# Power_Battery_Charger.net
KiCad netlist of a schematic drawn in Altium Designer
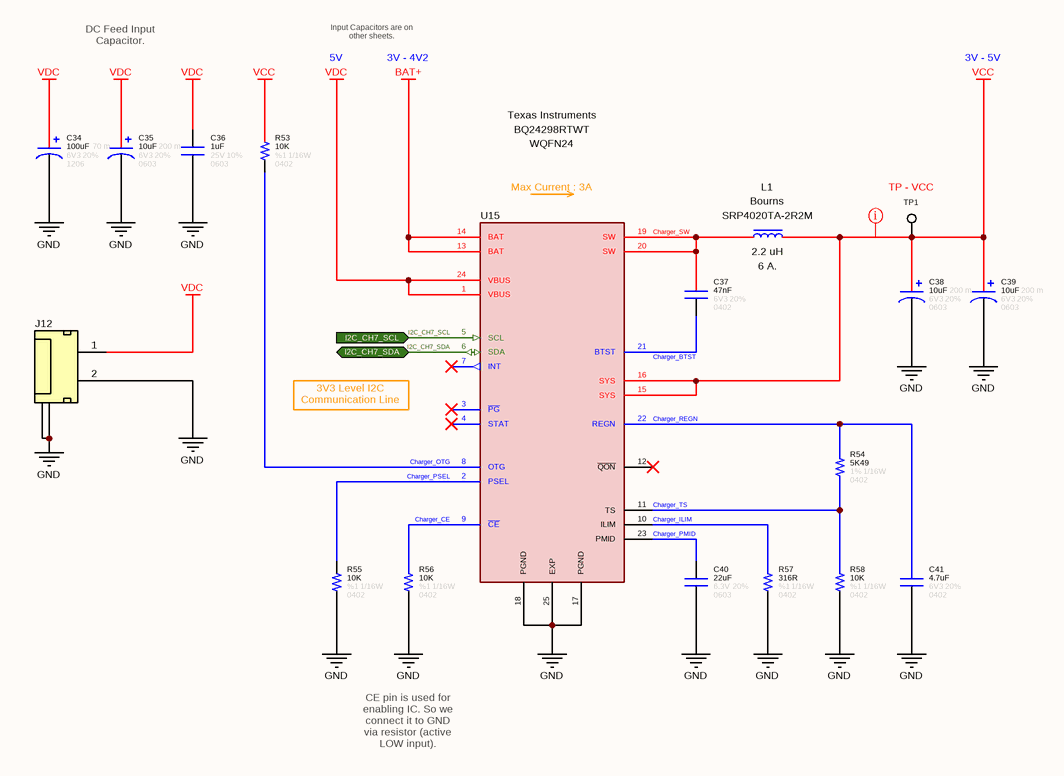
[diagram p0: Power Battery Charger.SchDoc]

(export (version "E")
  (design (tool "Eeschema 10.0.6"))
  (components
    (comp (ref "C34")
      (value "100uF")
      (footprint "CAPACITOR_0603_Tantalum")
      (description "Tantalum Capacitors - Polymer 6.3V 100uF 1206 20% ESR=70mOhms")
      (fields
        (field (name "MANUFACTURER PART NUMBER") "T527I107M006ATE070")
        (field (name "ESR") "70 m")
        (field (name "TOLERANCE") "20%")
        (field (name "CASE") "1206")
        (field (name "VOLTAGE") "6V3")
        (field (name "Comment") "Capacitor - 100uF [1206] (Tantalum)")
      )
      (libsource (lib "Akkoyun") (part "Capacitor - 100uF [1206-6V3] (Tantalium)"))
    )
    (comp (ref "C35")
      (value "10uF")
      (footprint "CAPACITOR_0603_Tantalum")
      (description "Capacitor - 10uF [0603] (Tantalium)")
      (fields
        (field (name "MANUFACTURER PART NUMBER") "F380J106MMAAH3")
        (field (name "ESR") "200 m")
        (field (name "TOLERANCE") "20%")
        (field (name "CASE") "0603")
        (field (name "VOLTAGE") "6V3")
        (field (name "Comment") "Capacitor - 10uF [0603] (Tantalum)")
      )
      (libsource (lib "Akkoyun") (part "Capacitor - 10uF [0603-6V3] (Tantalium)"))
    )
    (comp (ref "C36")
      (value "1uF")
      (footprint "CAPACITOR_0603")
      (description "Multilayer Ceramic Capacitors - SMD - 25V 1uF X7R 0603 10%")
      (fields
        (field (name "MANUFACTURER PART NUMBER") "GCJ188R71E105KA01D")
        (field (name "TOLERANCE") "10%")
        (field (name "CASE") "0603")
        (field (name "VOLTAGE") "25V")
        (field (name "Comment") "Capacitor - 1uF [0603] (Ceramic)")
      )
      (libsource (lib "Akkoyun") (part "Capacitor - 1uF [0603-25V]"))
    )
    (comp (ref "C37")
      (value "47nF")
      (footprint "CAPACITOR_0402")
      (description "Multilayer Ceramic Capacitors - SMD - 6.3V 47nF X7R 0402 10%")
      (fields
        (field (name "MANUFACTURER PART NUMBER") "04026C472MAT2A")
        (field (name "TOLERANCE") "20%")
        (field (name "CASE") "0402")
        (field (name "VOLTAGE") "6V3")
        (field (name "Comment") "Capacitor - 47nF [0402] (Ceramic)")
      )
      (libsource (lib "Akkoyun") (part "Capacitor - 47nF [0402-6V3]"))
    )
    (comp (ref "C38")
      (value "10uF")
      (footprint "CAPACITOR_0603_Tantalum")
      (description "Capacitor - 10uF [0603] (Tantalium)")
      (fields
        (field (name "MANUFACTURER PART NUMBER") "F380J106MMAAH3")
        (field (name "ESR") "200 m")
        (field (name "TOLERANCE") "20%")
        (field (name "CASE") "0603")
        (field (name "VOLTAGE") "6V3")
        (field (name "Comment") "Capacitor - 10uF [0603] (Tantalum)")
      )
      (libsource (lib "Akkoyun") (part "Capacitor - 10uF [0603-6V3] (Tantalium)"))
    )
    (comp (ref "C39")
      (value "10uF")
      (footprint "CAPACITOR_0603_Tantalum")
      (description "Capacitor - 10uF [0603] (Tantalium)")
      (fields
        (field (name "MANUFACTURER PART NUMBER") "F380J106MMAAH3")
        (field (name "ESR") "200 m")
        (field (name "TOLERANCE") "20%")
        (field (name "CASE") "0603")
        (field (name "VOLTAGE") "6V3")
        (field (name "Comment") "Capacitor - 10uF [0603] (Tantalum)")
      )
      (libsource (lib "Akkoyun") (part "Capacitor - 10uF [0603-6V3] (Tantalium)"))
    )
    (comp (ref "C40")
      (value "22uF")
      (footprint "CAPACITOR_0603")
      (description "Multilayer Ceramic Capacitors - SMD - 6V3 22uF X5R 0603 20%")
      (fields
        (field (name "MANUFACTURER PART NUMBER") "GRM188R60J226MEA0D")
        (field (name "TOLERANCE") "20%")
        (field (name "CASE") "0603")
        (field (name "VOLTAGE") "6.3V")
        (field (name "Comment") "Capacitor - 22uF [0603] (Ceramic)")
      )
      (libsource (lib "Akkoyun") (part "Capacitor - 22uF [0603-6V3]"))
    )
    (comp (ref "C41")
      (value "4.7uF")
      (footprint "CAPACITOR_0402")
      (description "Multilayer Ceramic Capacitors - SMD - 6V3 4.7uF X5R 0402 20%")
      (fields
        (field (name "MANUFACTURER PART NUMBER") "C0402C475M9PACTU")
        (field (name "TOLERANCE") "20%")
        (field (name "CASE") "0402")
        (field (name "VOLTAGE") "6V3")
        (field (name "Comment") "Capacitor - 4.7uF [0402] (Ceramic)")
      )
      (libsource (lib "Akkoyun") (part "Capacitor - 4.7uF [0402-6V3]"))
    )
    (comp (ref "J12")
      (value "2P SMD Tunic Connector")
      (footprint "Connector_Tunic 2P")
      (description "Mini Tunic Connector with 2P")
      (fields
        (field (name "MANUFACTURER PART NUMBER") "53261-0271")
        (field (name "MOUSER PART NUMBER") "538-53261-0271")
      )
      (libsource (lib "Akkoyun") (part "Connector - Mini Tunic 2P (1.25)"))
    )
    (comp (ref "L1")
      (value "2.2 uH")
      (footprint "SRP4020TA")
      (description "6 A. 2.2uH Power inducator, 20% tol, SMD, RoHS")
      (fields
        (field (name "TOLERANCE") "20%")
        (field (name "MANUFACTURER NAME") "Bourns")
        (field (name "MANUFACTURER PART NUMBER") "SRP4020TA-2R2M")
        (field (name "MAXIMUM DC CURRENT") "6 A.")
        (field (name "Comment") "SRP4020TA-2R2M")
      )
      (libsource (lib "Akkoyun") (part "Inductor - SRP4020TA-2R2M"))
    )
    (comp (ref "R53")
      (value "10K")
      (footprint "RESISTOR_0402")
      (description "Thick Film Resistors - SMD 1/16 W 10 KOhm 1%")
      (fields
        (field (name "MANUFACTURER PART NUMBER") "CRCW040210K0FKED")
        (field (name "TOLERANCE") "%1")
        (field (name "CASE") "0402")
        (field (name "POWER") "1/16W")
        (field (name "Comment") "10K - 0402 - %1 - 1/16W")
      )
      (libsource (lib "Akkoyun") (part "Resistor - 10K [0402]"))
    )
    (comp (ref "R54")
      (value "5K49")
      (footprint "RESISTOR_0402")
      (description "Thick Film Resistors - SMD 1/16 W 5.49 KOhm 1%")
      (fields
        (field (name "MANUFACTURER PART NUMBER") "CRCW04025K49FKED")
        (field (name "POWER") "1/16W")
        (field (name "CASE") "0402")
        (field (name "TOLERANCE") "1%")
        (field (name "Comment") "5K49 - 0402 - %1 - 1/16W")
      )
      (libsource (lib "Akkoyun") (part "Resistor - 5K49 [0402]"))
    )
    (comp (ref "R55")
      (value "10K")
      (footprint "RESISTOR_0402")
      (description "Thick Film Resistors - SMD 1/16 W 10 KOhm 1%")
      (fields
        (field (name "MANUFACTURER PART NUMBER") "CRCW040210K0FKED")
        (field (name "TOLERANCE") "%1")
        (field (name "CASE") "0402")
        (field (name "POWER") "1/16W")
        (field (name "Comment") "10K - 0402 - %1 - 1/16W")
      )
      (libsource (lib "Akkoyun") (part "Resistor - 10K [0402]"))
    )
    (comp (ref "R56")
      (value "10K")
      (footprint "RESISTOR_0402")
      (description "Thick Film Resistors - SMD 1/16 W 10 KOhm 1%")
      (fields
        (field (name "MANUFACTURER PART NUMBER") "CRCW040210K0FKED")
        (field (name "TOLERANCE") "%1")
        (field (name "CASE") "0402")
        (field (name "POWER") "1/16W")
        (field (name "Comment") "10K - 0402 - %1 - 1/16W")
      )
      (libsource (lib "Akkoyun") (part "Resistor - 10K [0402]"))
    )
    (comp (ref "R57")
      (value "316R")
      (footprint "RESISTOR_0402")
      (description "Thick Film Resistors - SMD 1/16 W 316 Ohm 1%")
      (fields
        (field (name "MANUFACTURER PART NUMBER") "CRCW0402316RFKED")
        (field (name "POWER") "1/16W")
        (field (name "CASE") "0402")
        (field (name "TOLERANCE") "%1")
        (field (name "Comment") "316R - 0402 - %1 - 1/16W")
      )
      (libsource (lib "Akkoyun") (part "Resistor - 316R [0402]"))
    )
    (comp (ref "R58")
      (value "10K")
      (footprint "RESISTOR_0402")
      (description "Thick Film Resistors - SMD 1/16 W 10 KOhm 1%")
      (fields
        (field (name "MANUFACTURER PART NUMBER") "CRCW040210K0FKED")
        (field (name "TOLERANCE") "%1")
        (field (name "CASE") "0402")
        (field (name "POWER") "1/16W")
        (field (name "Comment") "10K - 0402 - %1 - 1/16W")
      )
      (libsource (lib "Akkoyun") (part "Resistor - 10K [0402]"))
    )
    (comp (ref "TP1")
      (value "TP - VCC")
      (footprint "TP")
      (description "Test Point")
      (libsource (lib "Akkoyun") (part "PCB - Test Point"))
    )
    (comp (ref "U15")
      (value "BQ24298RTWT")
      (footprint "WQFN-24")
      (description "I2C Controlled 3A Single Cell Charger")
      (fields
        (field (name "MANUFACTURER NAME") "Texas Instruments")
        (field (name "MANUFACTURER PART NUMBER") "BQ24298RTWT")
        (field (name "CASE") "WQFN24")
      )
      (libsource (lib "Akkoyun") (part "IC - BQ24298RTWT"))
    )
  )
  (nets
    (net (code "1") (name "/Charger_BTST") (class "Default")
      (node (ref "C37") (pin "1") (pinfunction "1_1") (pintype "passive"))
      (node (ref "U15") (pin "21") (pinfunction "BTST_21") (pintype "power_in"))
    )
    (net (code "2") (name "/Charger_CE") (class "Default")
      (node (ref "R56") (pin "2") (pinfunction "2_2") (pintype "passive"))
      (node (ref "U15") (pin "9") (pinfunction "~{CE}_9") (pintype "passive"))
    )
    (net (code "3") (name "/Charger_ILIM") (class "Default")
      (node (ref "R57") (pin "2") (pinfunction "2_2") (pintype "passive"))
      (node (ref "U15") (pin "10") (pinfunction "ILIM_10") (pintype "passive"))
    )
    (net (code "4") (name "/Charger_OTG") (class "Default")
      (node (ref "R53") (pin "1") (pinfunction "1_1") (pintype "passive"))
      (node (ref "U15") (pin "8") (pinfunction "OTG_8") (pintype "passive"))
    )
    (net (code "5") (name "/Charger_PMID") (class "Default")
      (node (ref "C40") (pin "2") (pinfunction "2_2") (pintype "passive"))
      (node (ref "U15") (pin "23") (pinfunction "PMID_23") (pintype "power_in"))
    )
    (net (code "6") (name "/Charger_PSEL") (class "Default")
      (node (ref "R55") (pin "2") (pinfunction "2_2") (pintype "passive"))
      (node (ref "U15") (pin "2") (pinfunction "PSEL_2") (pintype "passive"))
    )
    (net (code "7") (name "/Charger_REGN") (class "Default")
      (node (ref "C41") (pin "2") (pinfunction "2_2") (pintype "passive"))
      (node (ref "R54") (pin "2") (pinfunction "2_2") (pintype "passive"))
      (node (ref "U15") (pin "22") (pinfunction "REGN_22") (pintype "power_in"))
    )
    (net (code "8") (name "/Charger_SW") (class "Default")
      (node (ref "C37") (pin "2") (pinfunction "2_2") (pintype "passive"))
      (node (ref "L1") (pin "1") (pinfunction "1_1") (pintype "passive"))
      (node (ref "U15") (pin "19") (pinfunction "SW_19") (pintype "power_in"))
      (node (ref "U15") (pin "20") (pinfunction "SW_20") (pintype "power_in"))
    )
    (net (code "9") (name "/Charger_TS") (class "Default")
      (node (ref "R54") (pin "1") (pinfunction "1_1") (pintype "passive"))
      (node (ref "R58") (pin "2") (pinfunction "2_2") (pintype "passive"))
      (node (ref "U15") (pin "11") (pinfunction "TS_11") (pintype "passive"))
    )
    (net (code "10") (name "/I2C_CH7_SCL") (class "Default")
      (node (ref "U15") (pin "5") (pinfunction "SCL_5") (pintype "input"))
    )
    (net (code "11") (name "/I2C_CH7_SDA") (class "Default")
      (node (ref "U15") (pin "6") (pinfunction "SDA_6") (pintype "bidirectional"))
    )
    (net (code "12") (name "BAT+") (class "Default")
      (node (ref "U15") (pin "13") (pinfunction "BAT_13") (pintype "power_in"))
      (node (ref "U15") (pin "14") (pinfunction "BAT_14") (pintype "power_in"))
    )
    (net (code "13") (name "GND") (class "Default")
      (node (ref "C34") (pin "2") (pinfunction "2_2") (pintype "passive"))
      (node (ref "C35") (pin "2") (pinfunction "2_2") (pintype "passive"))
      (node (ref "C36") (pin "1") (pinfunction "1_1") (pintype "passive"))
      (node (ref "C38") (pin "2") (pinfunction "2_2") (pintype "passive"))
      (node (ref "C39") (pin "2") (pinfunction "2_2") (pintype "passive"))
      (node (ref "C40") (pin "1") (pinfunction "1_1") (pintype "passive"))
      (node (ref "C41") (pin "1") (pinfunction "1_1") (pintype "passive"))
      (node (ref "J12") (pin "2") (pinfunction "Pin2_2") (pintype "power_in"))
      (node (ref "J12") (pin "3") (pinfunction "GND_3") (pintype "passive"))
      (node (ref "J12") (pin "4") (pinfunction "GND_4") (pintype "passive"))
      (node (ref "R55") (pin "1") (pinfunction "1_1") (pintype "passive"))
      (node (ref "R56") (pin "1") (pinfunction "1_1") (pintype "passive"))
      (node (ref "R57") (pin "1") (pinfunction "1_1") (pintype "passive"))
      (node (ref "R58") (pin "1") (pinfunction "1_1") (pintype "passive"))
      (node (ref "U15") (pin "17") (pinfunction "PGND_17") (pintype "power_in"))
      (node (ref "U15") (pin "18") (pinfunction "PGND_18") (pintype "power_in"))
      (node (ref "U15") (pin "25") (pinfunction "EXP_25") (pintype "power_in"))
    )
    (net (code "14") (name "VCC") (class "Default")
      (node (ref "C38") (pin "1") (pinfunction "1_1") (pintype "passive"))
      (node (ref "C39") (pin "1") (pinfunction "1_1") (pintype "passive"))
      (node (ref "L1") (pin "2") (pinfunction "2_2") (pintype "passive"))
      (node (ref "R53") (pin "2") (pinfunction "2_2") (pintype "passive"))
      (node (ref "TP1") (pin "1") (pinfunction "1_1") (pintype "passive"))
      (node (ref "U15") (pin "15") (pinfunction "SYS_15") (pintype "power_in"))
      (node (ref "U15") (pin "16") (pinfunction "SYS_16") (pintype "power_in"))
    )
    (net (code "15") (name "VDC") (class "Default")
      (node (ref "C34") (pin "1") (pinfunction "1_1") (pintype "passive"))
      (node (ref "C35") (pin "1") (pinfunction "1_1") (pintype "passive"))
      (node (ref "C36") (pin "2") (pinfunction "2_2") (pintype "passive"))
      (node (ref "J12") (pin "1") (pinfunction "Pin1_1") (pintype "power_in"))
      (node (ref "U15") (pin "1") (pinfunction "VBUS_1") (pintype "power_in"))
      (node (ref "U15") (pin "24") (pinfunction "VBUS_24") (pintype "power_in"))
    )
    (net (code "16") (name "unconnected-(U15-INT-Pad7)") (class "Default")
      (node (ref "U15") (pin "7") (pinfunction "INT_7") (pintype "output+no_connect"))
    )
    (net (code "17") (name "unconnected-(U15-STAT-Pad4)") (class "Default")
      (node (ref "U15") (pin "4") (pinfunction "STAT_4") (pintype "open_collector+no_connect"))
    )
    (net (code "18") (name "unconnected-(U15-~{PG}-Pad3)") (class "Default")
      (node (ref "U15") (pin "3") (pinfunction "~{PG}_3") (pintype "open_collector+no_connect"))
    )
    (net (code "19") (name "unconnected-(U15-~{QON}-Pad12)") (class "Default")
      (node (ref "U15") (pin "12") (pinfunction "~{QON}_12") (pintype "passive+no_connect"))
    )
  )
)
